# Sheet3.net
KiCad netlist of a schematic drawn in Altium Designer
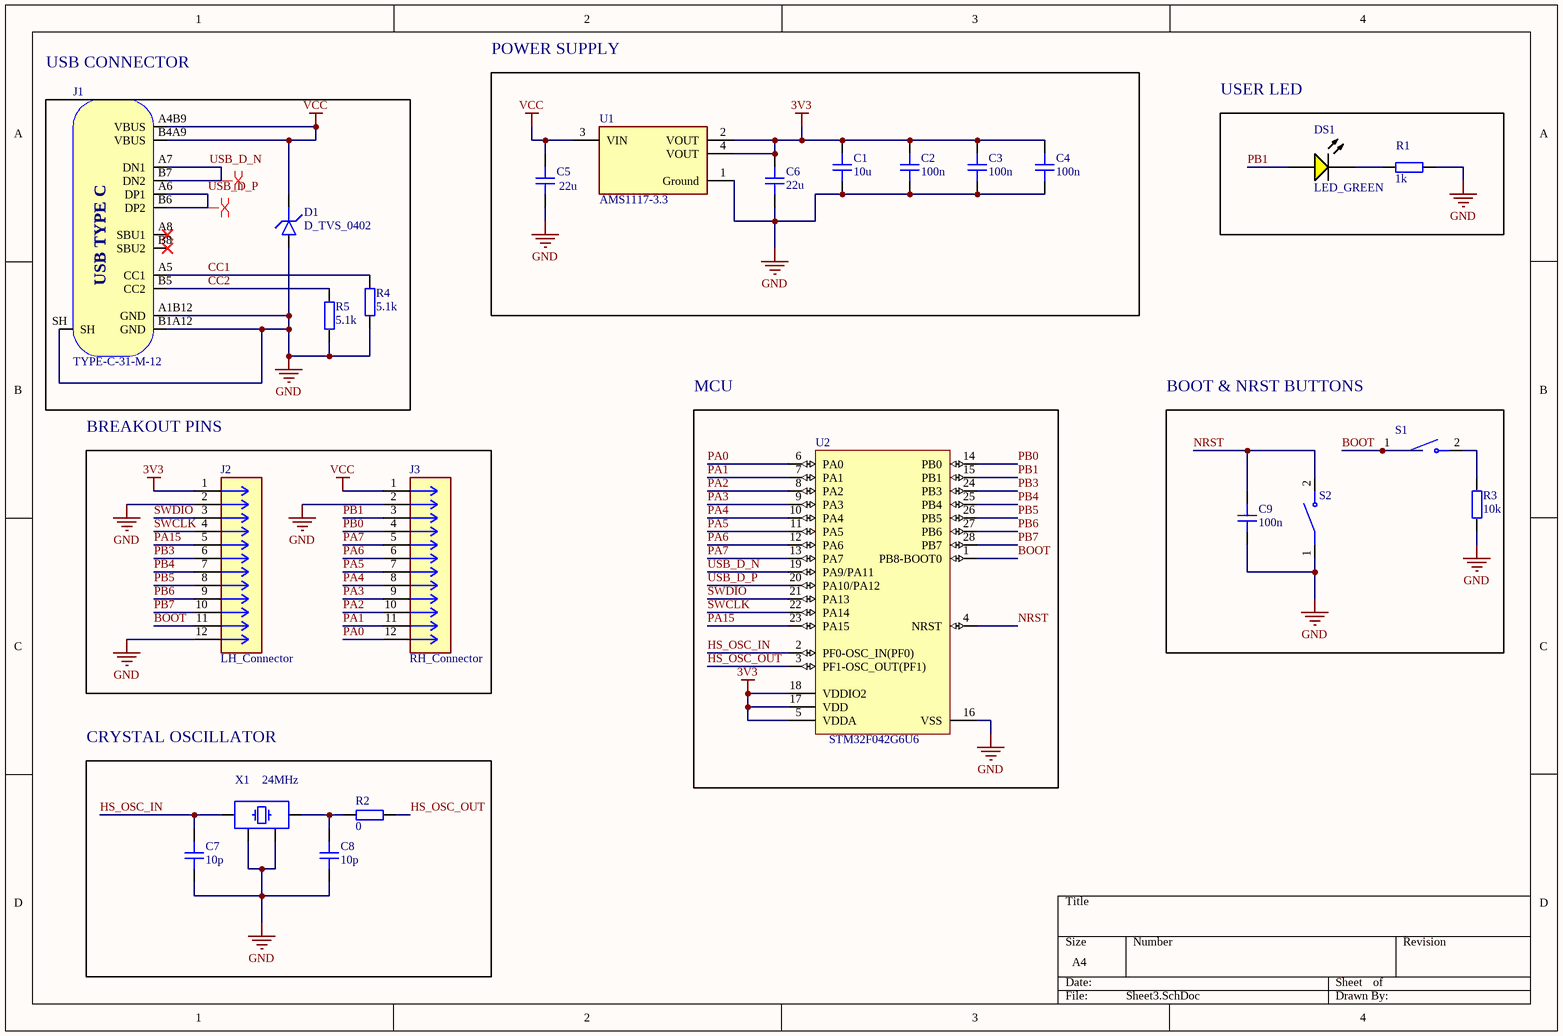
[diagram p0: Sheet3.SchDoc]

(export (version "E")
  (design (tool "Eeschema 10.0.6"))
  (components
    (comp (ref "C1")
      (value "10u")
      (footprint "CAP_0603")
      (description "Capacitor SMD 0603")
      (libsource (lib "Schematic-Lib-PhilsLab") (part "CAP_0603"))
    )
    (comp (ref "C2")
      (value "100n")
      (footprint "CAP_0402")
      (description "Capacitor SMD 0402")
      (libsource (lib "Schematic-Lib-PhilsLab") (part "CAP_0402"))
    )
    (comp (ref "C3")
      (value "100n")
      (footprint "CAP_0402")
      (description "Capacitor SMD 0402")
      (libsource (lib "Schematic-Lib-PhilsLab") (part "CAP_0402"))
    )
    (comp (ref "C4")
      (value "100n")
      (footprint "CAP_0402")
      (description "Capacitor SMD 0402")
      (libsource (lib "Schematic-Lib-PhilsLab") (part "CAP_0402"))
    )
    (comp (ref "C5")
      (value "22u")
      (footprint "CAP_0805")
      (description "Capacitor SMD 0805")
      (libsource (lib "Schematic-Lib-PhilsLab") (part "CAP_0805"))
    )
    (comp (ref "C6")
      (value "22u")
      (footprint "CAP_0805")
      (description "Capacitor SMD 0805")
      (libsource (lib "Schematic-Lib-PhilsLab") (part "CAP_0805"))
    )
    (comp (ref "C7")
      (value "10p")
      (footprint "CAP_0402")
      (description "Capacitor SMD 0402")
      (libsource (lib "Schematic-Lib-PhilsLab") (part "CAP_0402"))
    )
    (comp (ref "C8")
      (value "10p")
      (footprint "CAP_0402")
      (description "Capacitor SMD 0402")
      (libsource (lib "Schematic-Lib-PhilsLab") (part "CAP_0402"))
    )
    (comp (ref "C9")
      (value "100n")
      (footprint "CAP_0402")
      (description "Capacitor SMD 0402")
      (libsource (lib "Schematic-Lib-PhilsLab") (part "CAP_0402"))
    )
    (comp (ref "D1")
      (value "D_TVS_0402")
      (footprint "D_0402")
      (description "Diode TVS / ESD 0402")
      (libsource (lib "Schematic-Lib-PhilsLab") (part "D_TVS_0402"))
    )
    (comp (ref "DS1")
      (value "LED_GREEN")
      (footprint "EVRL-0603-2_V")
      (description "Chip LED, Yellow, 5 V, 25mA, -40 to 85 degC, 2-Pin SMD (0603), RoHS, Tape and Reel")
      (fields (field (name "MANUFACTURER") "Everlight Electronics"))
      (libsource (lib "Nicole Gray") (part "LED-YELLOW-AK-2"))
    )
    (comp (ref "J1")
      (value "TYPE-C-31-M-12")
      (footprint "TYPE-C-31-M-12")
      (description "USB Type C Connector Horizontal SMT")
      (fields (field (name "MANUFACTURER") "Koren Hroparts"))
      (libsource (lib "Schematic-Lib-PhilsLab") (part "TYPE-C-31-M-12"))
    )
    (comp (ref "J2")
      (value "LH_Connector")
      (footprint "CONN_SD-42375-001_M320_12_MOL")
      (fields (field (name "MP") "22284121"))
      (libsource (lib "Nicole Gray") (part "22284121"))
    )
    (comp (ref "J3")
      (value "RH_Connector")
      (footprint "CONN_SD-42375-001_M320_12_MOL")
      (fields (field (name "MP") "22284121"))
      (libsource (lib "Nicole Gray") (part "22284121"))
    )
    (comp (ref "R1")
      (value "1k")
      (footprint "RES_0402")
      (description "Resistor SMD 0402")
      (libsource (lib "Schematic-Lib-PhilsLab") (part "RES_0402"))
    )
    (comp (ref "R2")
      (value "0")
      (footprint "RES_0402")
      (description "Resistor SMD 0402")
      (libsource (lib "Schematic-Lib-PhilsLab") (part "RES_0402"))
    )
    (comp (ref "R3")
      (value "10k")
      (footprint "RES_0402")
      (description "Resistor SMD 0402")
      (libsource (lib "Schematic-Lib-PhilsLab") (part "RES_0402"))
    )
    (comp (ref "R4")
      (value "5.1k")
      (footprint "RES_0402")
      (description "Resistor SMD 0402")
      (libsource (lib "Schematic-Lib-PhilsLab") (part "RES_0402"))
    )
    (comp (ref "R5")
      (value "5.1k")
      (footprint "RES_0402")
      (description "Resistor SMD 0402")
      (libsource (lib "Schematic-Lib-PhilsLab") (part "RES_0402"))
    )
    (comp (ref "S1")
      (value "~")
      (footprint "SW_TS-1088-AR02016")
      (fields (field (name "MF") "Xunpu") (field (name "MP") "TS-1088-AR02016"))
      (libsource (lib "Nicole Gray") (part "TS-1088-AR02016"))
    )
    (comp (ref "S2")
      (value "~")
      (footprint "SW_TS-1088-AR02016")
      (fields (field (name "MF") "Xunpu") (field (name "MP") "TS-1088-AR02016"))
      (libsource (lib "Nicole Gray") (part "TS-1088-AR02016"))
    )
    (comp (ref "U1")
      (value "AMS1117-3.3")
      (footprint "FP-AMS1117-IPC_C")
      (description "LDO Voltage Regulators 1A, 3.3V")
      (fields
        (field (name "OCTOPART") "https://octopart.com/ams1117-3.3-advanced+monolithic+systems-25899300")
        (field (name "MANUFACTURER") "Advanced Monolithic Systems")
      )
      (libsource (lib "Altium Content Vault") (part "8bdbb5f8e77002000e30dd2845d0354"))
    )
    (comp (ref "U2")
      (value "STM32F042G6U6")
      (footprint "STM-UFQFPN28_V")
      (fields (field (name "MANUFACTURER") "STMicroelectronics"))
      (libsource (lib "Altium Content Vault") (part "MC-ARM-STM32F042-UFQFPN28"))
    )
    (comp (ref "X1")
      (value "24MHz")
      (footprint "XTAL_3225")
      (description "Crystal SMD 24MHz 10PPM 7pF 3225")
      (fields
        (field (name "MANUFACTURER") "Epson")
        (field (name "MANUFACTURER PART NUMBER") "TSX-3225 24.0000MF15X-AC")
      )
      (libsource (lib "Schematic-Lib-PhilsLab") (part "TSX-3225_24.0000MF15X-AC"))
    )
  )
  (nets
    (net (code "1") (name "/BOOT") (class "Default")
      (node (ref "J2") (pin "11") (pinfunction "11_11") (pintype "passive"))
      (node (ref "S1") (pin "1") (pinfunction "1_1") (pintype "passive"))
      (node (ref "U2") (pin "1") (pinfunction "PB8-BOOT0_1") (pintype "bidirectional"))
    )
    (net (code "2") (name "/CC1") (class "Default")
      (node (ref "J1") (pin "A5") (pinfunction "CC1_A5") (pintype "passive"))
      (node (ref "R4") (pin "1") (pinfunction "1_1") (pintype "passive"))
    )
    (net (code "3") (name "/CC2") (class "Default")
      (node (ref "J1") (pin "B5") (pinfunction "CC2_B5") (pintype "tri_state"))
      (node (ref "R5") (pin "2") (pinfunction "2_2") (pintype "passive"))
    )
    (net (code "4") (name "/HS_OSC_IN") (class "Default")
      (node (ref "C7") (pin "2") (pinfunction "2_2") (pintype "passive"))
      (node (ref "U2") (pin "2") (pinfunction "PF0-OSC_IN(PF0)_2") (pintype "bidirectional"))
      (node (ref "X1") (pin "1") (pinfunction "1_1") (pintype "passive"))
    )
    (net (code "5") (name "/HS_OSC_OUT") (class "Default")
      (node (ref "R2") (pin "1") (pinfunction "1_1") (pintype "passive"))
      (node (ref "U2") (pin "3") (pinfunction "PF1-OSC_OUT(PF1)_3") (pintype "bidirectional"))
    )
    (net (code "6") (name "/NRST") (class "Default")
      (node (ref "C9") (pin "2") (pinfunction "2_2") (pintype "passive"))
      (node (ref "S2") (pin "2") (pinfunction "2_2") (pintype "passive"))
      (node (ref "U2") (pin "4") (pinfunction "NRST_4") (pintype "bidirectional"))
    )
    (net (code "7") (name "/PA0") (class "Default")
      (node (ref "J3") (pin "12") (pinfunction "12_12") (pintype "passive"))
      (node (ref "U2") (pin "6") (pinfunction "PA0_6") (pintype "bidirectional"))
    )
    (net (code "8") (name "/PA1") (class "Default")
      (node (ref "J3") (pin "11") (pinfunction "11_11") (pintype "passive"))
      (node (ref "U2") (pin "7") (pinfunction "PA1_7") (pintype "bidirectional"))
    )
    (net (code "9") (name "/PA2") (class "Default")
      (node (ref "J3") (pin "10") (pinfunction "10_10") (pintype "passive"))
      (node (ref "U2") (pin "8") (pinfunction "PA2_8") (pintype "bidirectional"))
    )
    (net (code "10") (name "/PA3") (class "Default")
      (node (ref "J3") (pin "9") (pinfunction "9_9") (pintype "passive"))
      (node (ref "U2") (pin "9") (pinfunction "PA3_9") (pintype "bidirectional"))
    )
    (net (code "11") (name "/PA4") (class "Default")
      (node (ref "J3") (pin "8") (pinfunction "8_8") (pintype "passive"))
      (node (ref "U2") (pin "10") (pinfunction "PA4_10") (pintype "bidirectional"))
    )
    (net (code "12") (name "/PA5") (class "Default")
      (node (ref "J3") (pin "7") (pinfunction "7_7") (pintype "passive"))
      (node (ref "U2") (pin "11") (pinfunction "PA5_11") (pintype "bidirectional"))
    )
    (net (code "13") (name "/PA6") (class "Default")
      (node (ref "J3") (pin "6") (pinfunction "6_6") (pintype "passive"))
      (node (ref "U2") (pin "12") (pinfunction "PA6_12") (pintype "bidirectional"))
    )
    (net (code "14") (name "/PA7") (class "Default")
      (node (ref "J3") (pin "5") (pinfunction "5_5") (pintype "passive"))
      (node (ref "U2") (pin "13") (pinfunction "PA7_13") (pintype "bidirectional"))
    )
    (net (code "15") (name "/PA15") (class "Default")
      (node (ref "J2") (pin "5") (pinfunction "5_5") (pintype "passive"))
      (node (ref "U2") (pin "23") (pinfunction "PA15_23") (pintype "bidirectional"))
    )
    (net (code "16") (name "/PB0") (class "Default")
      (node (ref "J3") (pin "4") (pinfunction "4_4") (pintype "passive"))
      (node (ref "U2") (pin "14") (pinfunction "PB0_14") (pintype "bidirectional"))
    )
    (net (code "17") (name "/PB1") (class "Default")
      (node (ref "DS1") (pin "1") (pinfunction "A_1") (pintype "passive"))
      (node (ref "J3") (pin "3") (pinfunction "3_3") (pintype "passive"))
      (node (ref "U2") (pin "15") (pinfunction "PB1_15") (pintype "bidirectional"))
    )
    (net (code "18") (name "/PB3") (class "Default")
      (node (ref "J2") (pin "6") (pinfunction "6_6") (pintype "passive"))
      (node (ref "U2") (pin "24") (pinfunction "PB3_24") (pintype "bidirectional"))
    )
    (net (code "19") (name "/PB4") (class "Default")
      (node (ref "J2") (pin "7") (pinfunction "7_7") (pintype "passive"))
      (node (ref "U2") (pin "25") (pinfunction "PB4_25") (pintype "bidirectional"))
    )
    (net (code "20") (name "/PB5") (class "Default")
      (node (ref "J2") (pin "8") (pinfunction "8_8") (pintype "passive"))
      (node (ref "U2") (pin "26") (pinfunction "PB5_26") (pintype "bidirectional"))
    )
    (net (code "21") (name "/PB6") (class "Default")
      (node (ref "J2") (pin "9") (pinfunction "9_9") (pintype "passive"))
      (node (ref "U2") (pin "27") (pinfunction "PB6_27") (pintype "bidirectional"))
    )
    (net (code "22") (name "/PB7") (class "Default")
      (node (ref "J2") (pin "10") (pinfunction "10_10") (pintype "passive"))
      (node (ref "U2") (pin "28") (pinfunction "PB7_28") (pintype "bidirectional"))
    )
    (net (code "23") (name "/SWCLK") (class "Default")
      (node (ref "J2") (pin "4") (pinfunction "4_4") (pintype "passive"))
      (node (ref "U2") (pin "22") (pinfunction "PA14_22") (pintype "bidirectional"))
    )
    (net (code "24") (name "/SWDIO") (class "Default")
      (node (ref "J2") (pin "3") (pinfunction "3_3") (pintype "passive"))
      (node (ref "U2") (pin "21") (pinfunction "PA13_21") (pintype "bidirectional"))
    )
    (net (code "25") (name "/USB_D_N") (class "Default")
      (node (ref "J1") (pin "A7") (pinfunction "DN1_A7") (pintype "bidirectional"))
      (node (ref "J1") (pin "B7") (pinfunction "DN2_B7") (pintype "bidirectional"))
      (node (ref "U2") (pin "19") (pinfunction "PA9/PA11_19") (pintype "bidirectional"))
    )
    (net (code "26") (name "/USB_D_P") (class "Default")
      (node (ref "J1") (pin "A6") (pinfunction "DP1_A6") (pintype "bidirectional"))
      (node (ref "J1") (pin "B6") (pinfunction "DP2_B6") (pintype "bidirectional"))
      (node (ref "U2") (pin "20") (pinfunction "PA10/PA12_20") (pintype "bidirectional"))
    )
    (net (code "27") (name "3V3") (class "Default")
      (node (ref "C1") (pin "2") (pinfunction "2_2") (pintype "passive"))
      (node (ref "C2") (pin "2") (pinfunction "2_2") (pintype "passive"))
      (node (ref "C3") (pin "2") (pinfunction "2_2") (pintype "passive"))
      (node (ref "C4") (pin "2") (pinfunction "2_2") (pintype "passive"))
      (node (ref "C6") (pin "2") (pinfunction "2_2") (pintype "passive"))
      (node (ref "J2") (pin "1") (pinfunction "1_1") (pintype "passive"))
      (node (ref "U1") (pin "2") (pinfunction "VOUT_2") (pintype "passive"))
      (node (ref "U1") (pin "4") (pinfunction "VOUT_4") (pintype "passive"))
      (node (ref "U2") (pin "17") (pinfunction "VDD_17") (pintype "power_in"))
      (node (ref "U2") (pin "18") (pinfunction "VDDIO2_18") (pintype "power_in"))
      (node (ref "U2") (pin "5") (pinfunction "VDDA_5") (pintype "power_in"))
    )
    (net (code "28") (name "GND") (class "Default")
      (node (ref "C1") (pin "1") (pinfunction "1_1") (pintype "passive"))
      (node (ref "C2") (pin "1") (pinfunction "1_1") (pintype "passive"))
      (node (ref "C3") (pin "1") (pinfunction "1_1") (pintype "passive"))
      (node (ref "C4") (pin "1") (pinfunction "1_1") (pintype "passive"))
      (node (ref "C5") (pin "1") (pinfunction "1_1") (pintype "passive"))
      (node (ref "C6") (pin "1") (pinfunction "1_1") (pintype "passive"))
      (node (ref "C7") (pin "1") (pinfunction "1_1") (pintype "passive"))
      (node (ref "C8") (pin "1") (pinfunction "1_1") (pintype "passive"))
      (node (ref "C9") (pin "1") (pinfunction "1_1") (pintype "passive"))
      (node (ref "D1") (pin "A") (pinfunction "A_A") (pintype "passive"))
      (node (ref "J1") (pin "A1B12") (pinfunction "GND_A1B12") (pintype "power_in"))
      (node (ref "J1") (pin "B1A12") (pinfunction "GND_B1A12") (pintype "power_in"))
      (node (ref "J1") (pin "SH") (pinfunction "SH_SH") (pintype "power_in"))
      (node (ref "J2") (pin "12") (pinfunction "12_12") (pintype "passive"))
      (node (ref "J2") (pin "2") (pinfunction "2_2") (pintype "passive"))
      (node (ref "J3") (pin "2") (pinfunction "2_2") (pintype "passive"))
      (node (ref "R1") (pin "2") (pinfunction "2_2") (pintype "passive"))
      (node (ref "R3") (pin "2") (pinfunction "2_2") (pintype "passive"))
      (node (ref "R4") (pin "2") (pinfunction "2_2") (pintype "passive"))
      (node (ref "R5") (pin "1") (pinfunction "1_1") (pintype "passive"))
      (node (ref "S2") (pin "1") (pinfunction "1_1") (pintype "passive"))
      (node (ref "U1") (pin "1") (pinfunction "Ground_1") (pintype "power_in"))
      (node (ref "U2") (pin "16") (pinfunction "VSS_16") (pintype "power_in"))
      (node (ref "X1") (pin "2") (pinfunction "2_2") (pintype "passive"))
      (node (ref "X1") (pin "4") (pinfunction "4_4") (pintype "passive"))
    )
    (net (code "29") (name "Net-(C8-Pad2)") (class "Default")
      (node (ref "C8") (pin "2") (pinfunction "2_2") (pintype "passive"))
      (node (ref "R2") (pin "2") (pinfunction "2_2") (pintype "passive"))
      (node (ref "X1") (pin "3") (pinfunction "3_3") (pintype "passive"))
    )
    (net (code "30") (name "Net-(DS1-K)") (class "Default")
      (node (ref "DS1") (pin "2") (pinfunction "K_2") (pintype "passive"))
      (node (ref "R1") (pin "1") (pinfunction "1_1") (pintype "passive"))
    )
    (net (code "31") (name "Net-(R3-Pad1)") (class "Default")
      (node (ref "R3") (pin "1") (pinfunction "1_1") (pintype "passive"))
      (node (ref "S1") (pin "2") (pinfunction "2_2") (pintype "passive"))
    )
    (net (code "32") (name "VCC") (class "Default")
      (node (ref "C5") (pin "2") (pinfunction "2_2") (pintype "passive"))
      (node (ref "D1") (pin "K") (pinfunction "K_K") (pintype "passive"))
      (node (ref "J1") (pin "A4B9") (pinfunction "VBUS_A4B9") (pintype "power_in"))
      (node (ref "J1") (pin "B4A9") (pinfunction "VBUS_B4A9") (pintype "power_in"))
      (node (ref "J3") (pin "1") (pinfunction "1_1") (pintype "passive"))
      (node (ref "U1") (pin "3") (pinfunction "VIN_3") (pintype "power_in"))
    )
    (net (code "33") (name "unconnected-(J1-SBU1-PadA8)") (class "Default")
      (node (ref "J1") (pin "A8") (pinfunction "SBU1_A8") (pintype "bidirectional+no_connect"))
    )
    (net (code "34") (name "unconnected-(J1-SBU2-PadB8)") (class "Default")
      (node (ref "J1") (pin "B8") (pinfunction "SBU2_B8") (pintype "bidirectional+no_connect"))
    )
  )
)
